# vmuzero_SEPS525_V1_0_ICHG100.net
KiCad netlist of a schematic drawn in EAGLE
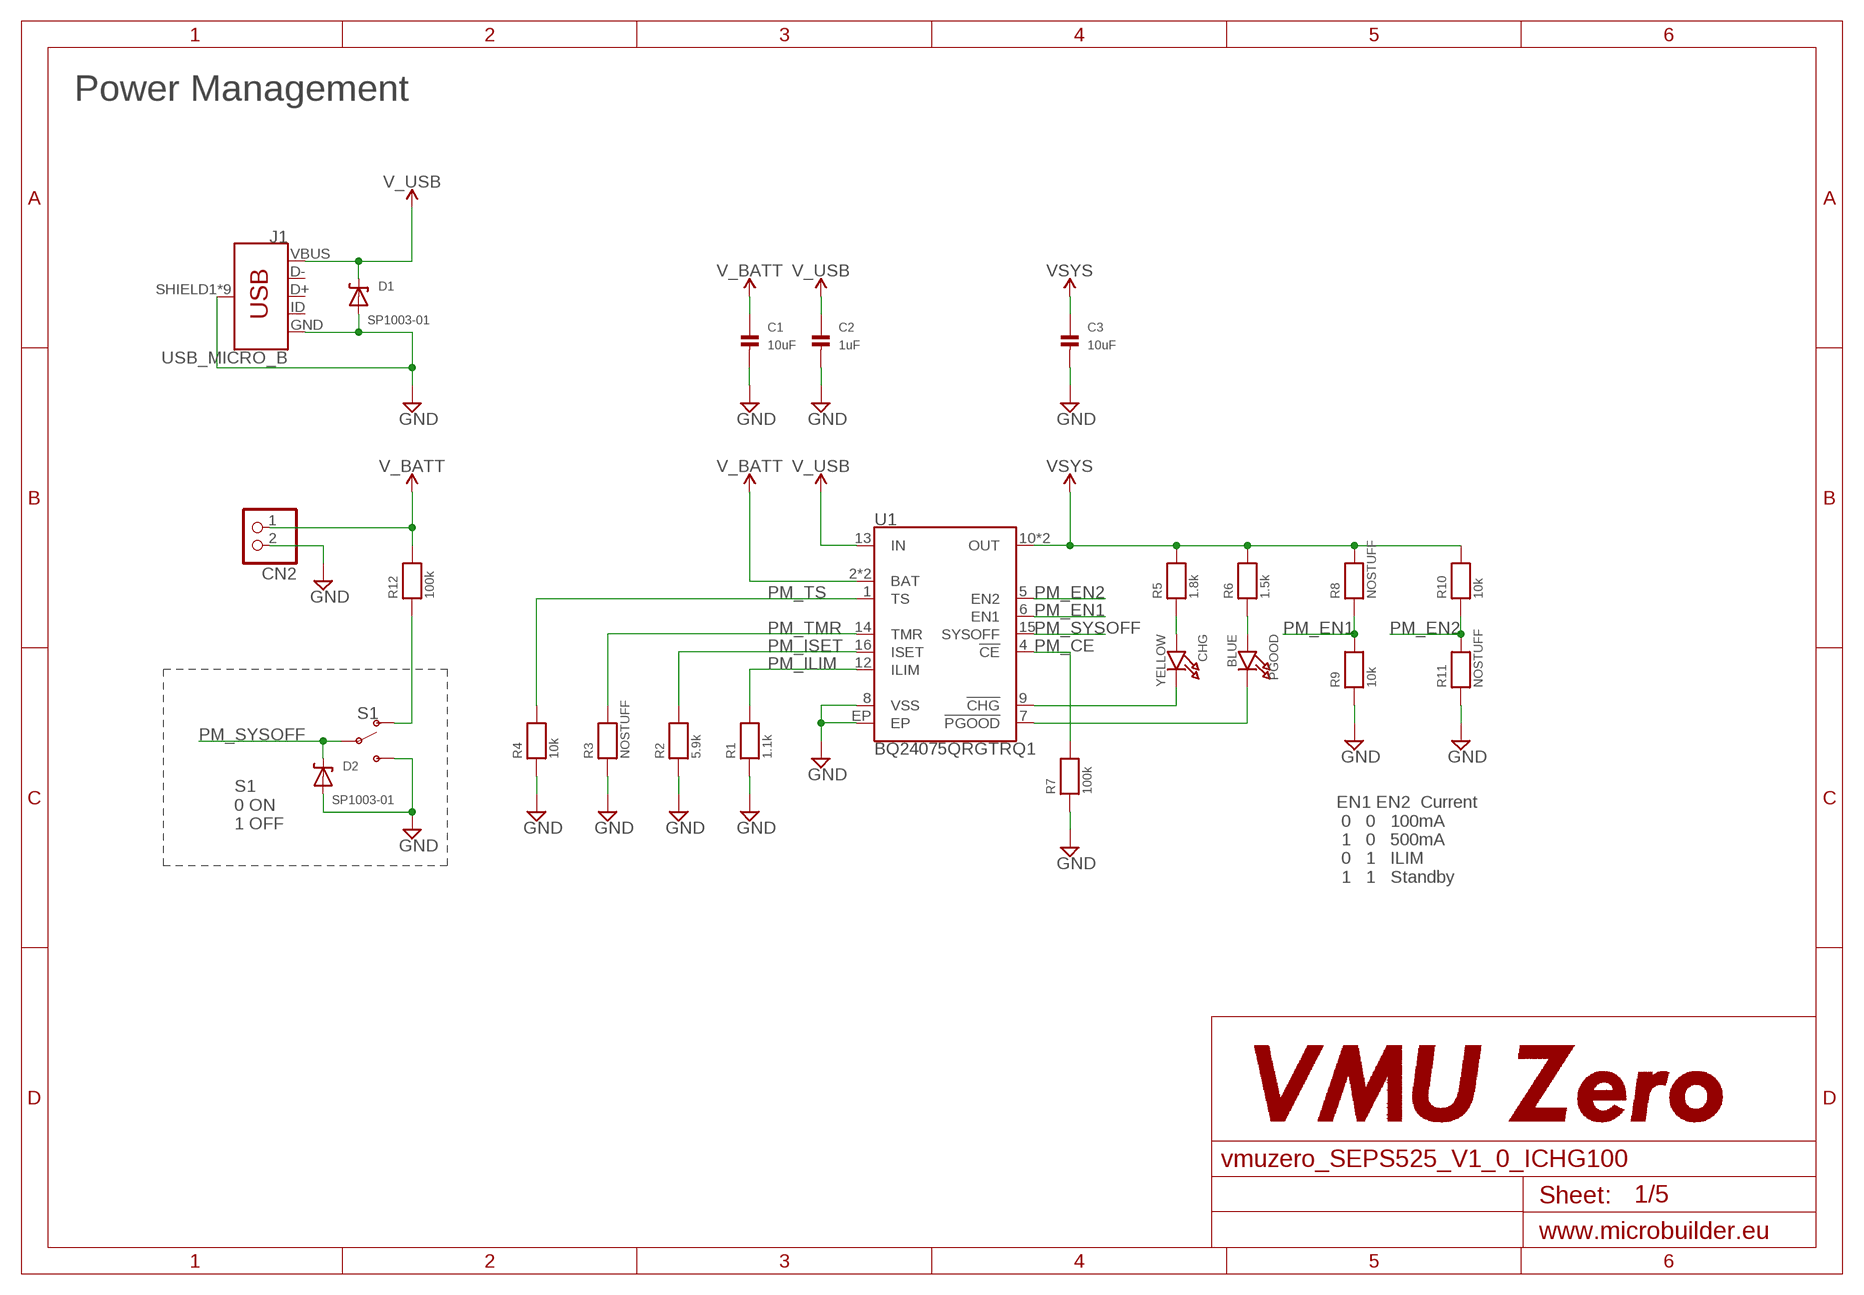
[diagram p0: schematic, sheet 1]
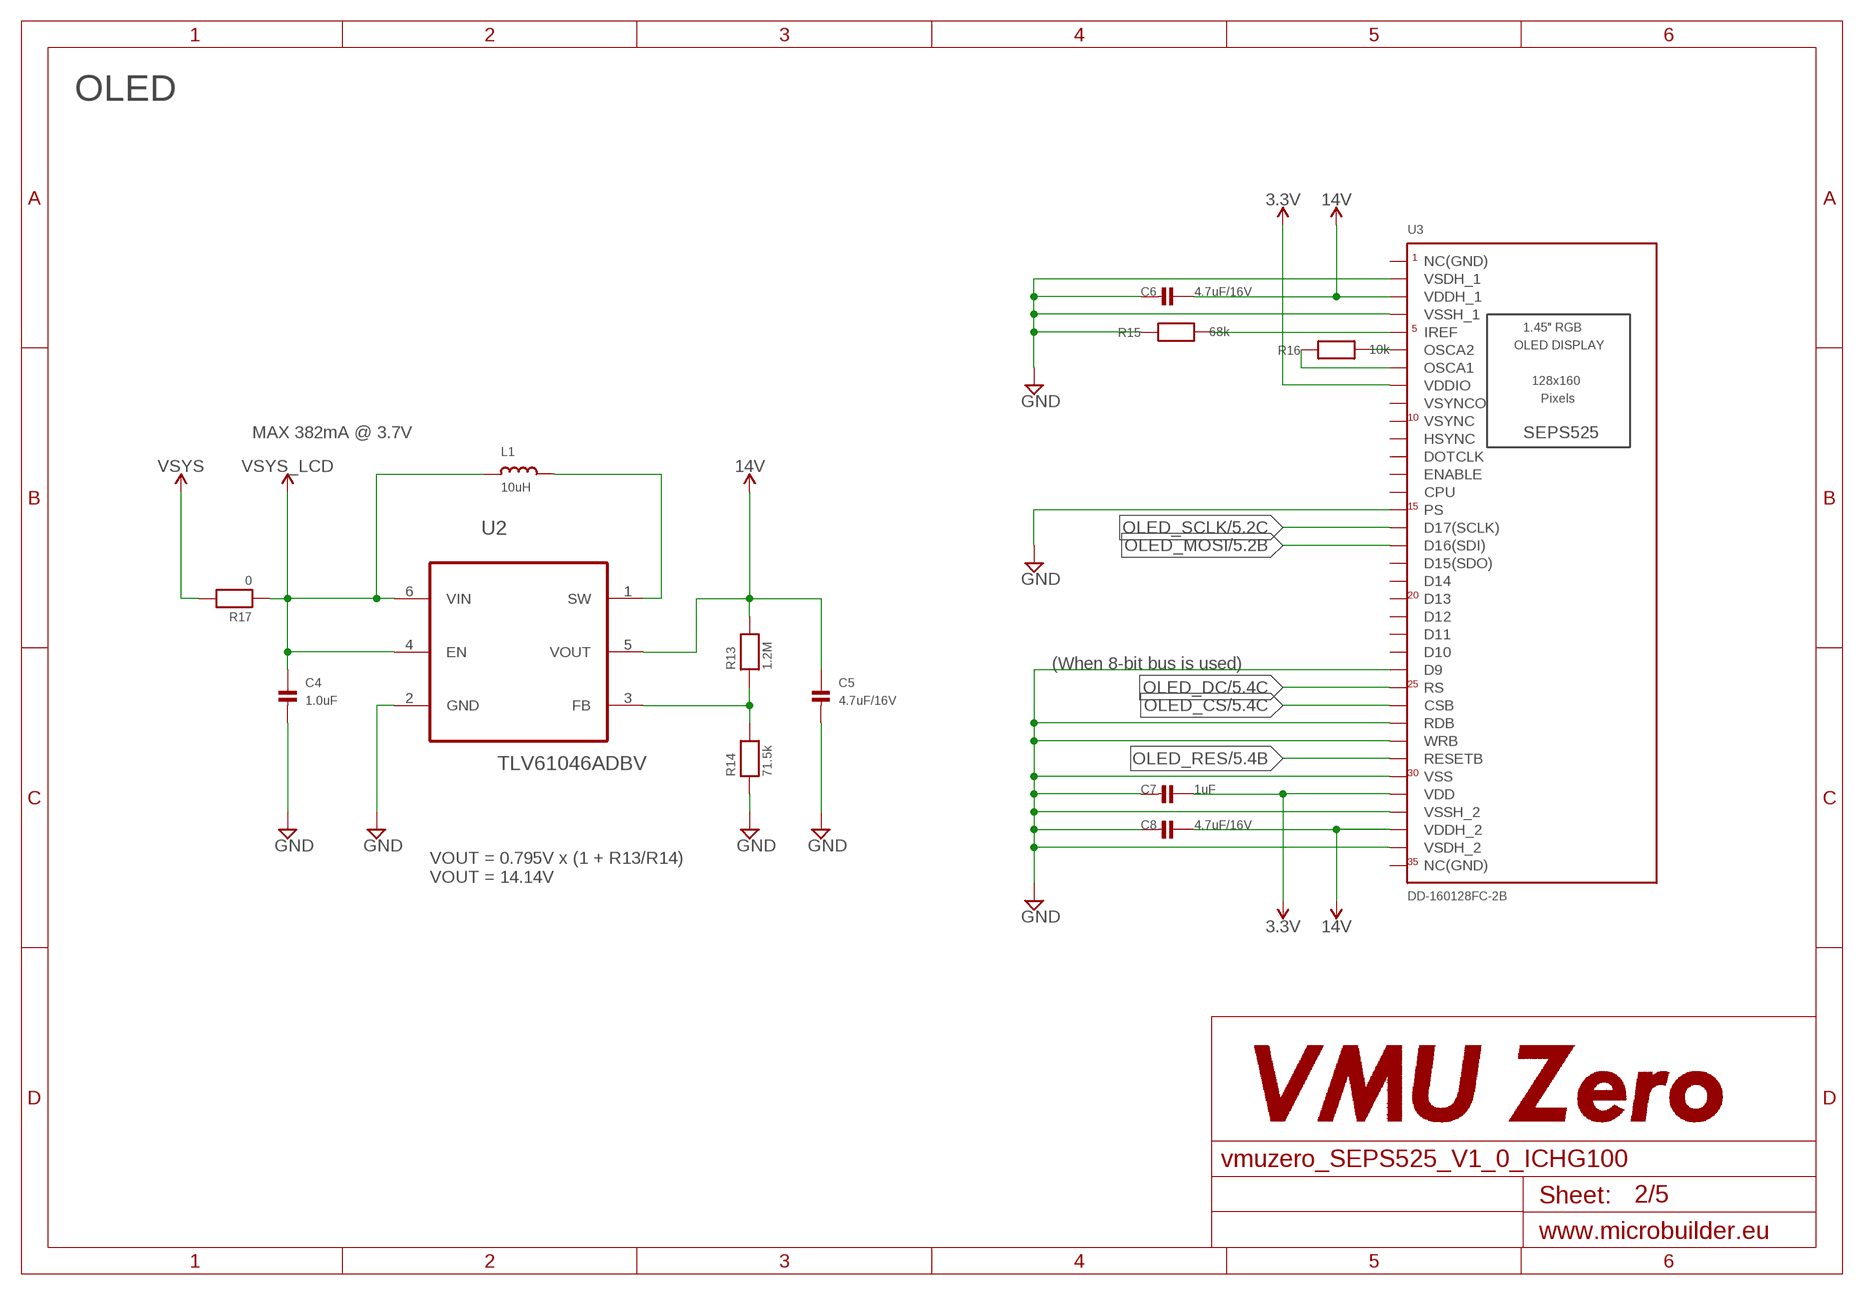
[diagram p1: schematic, sheet 2]
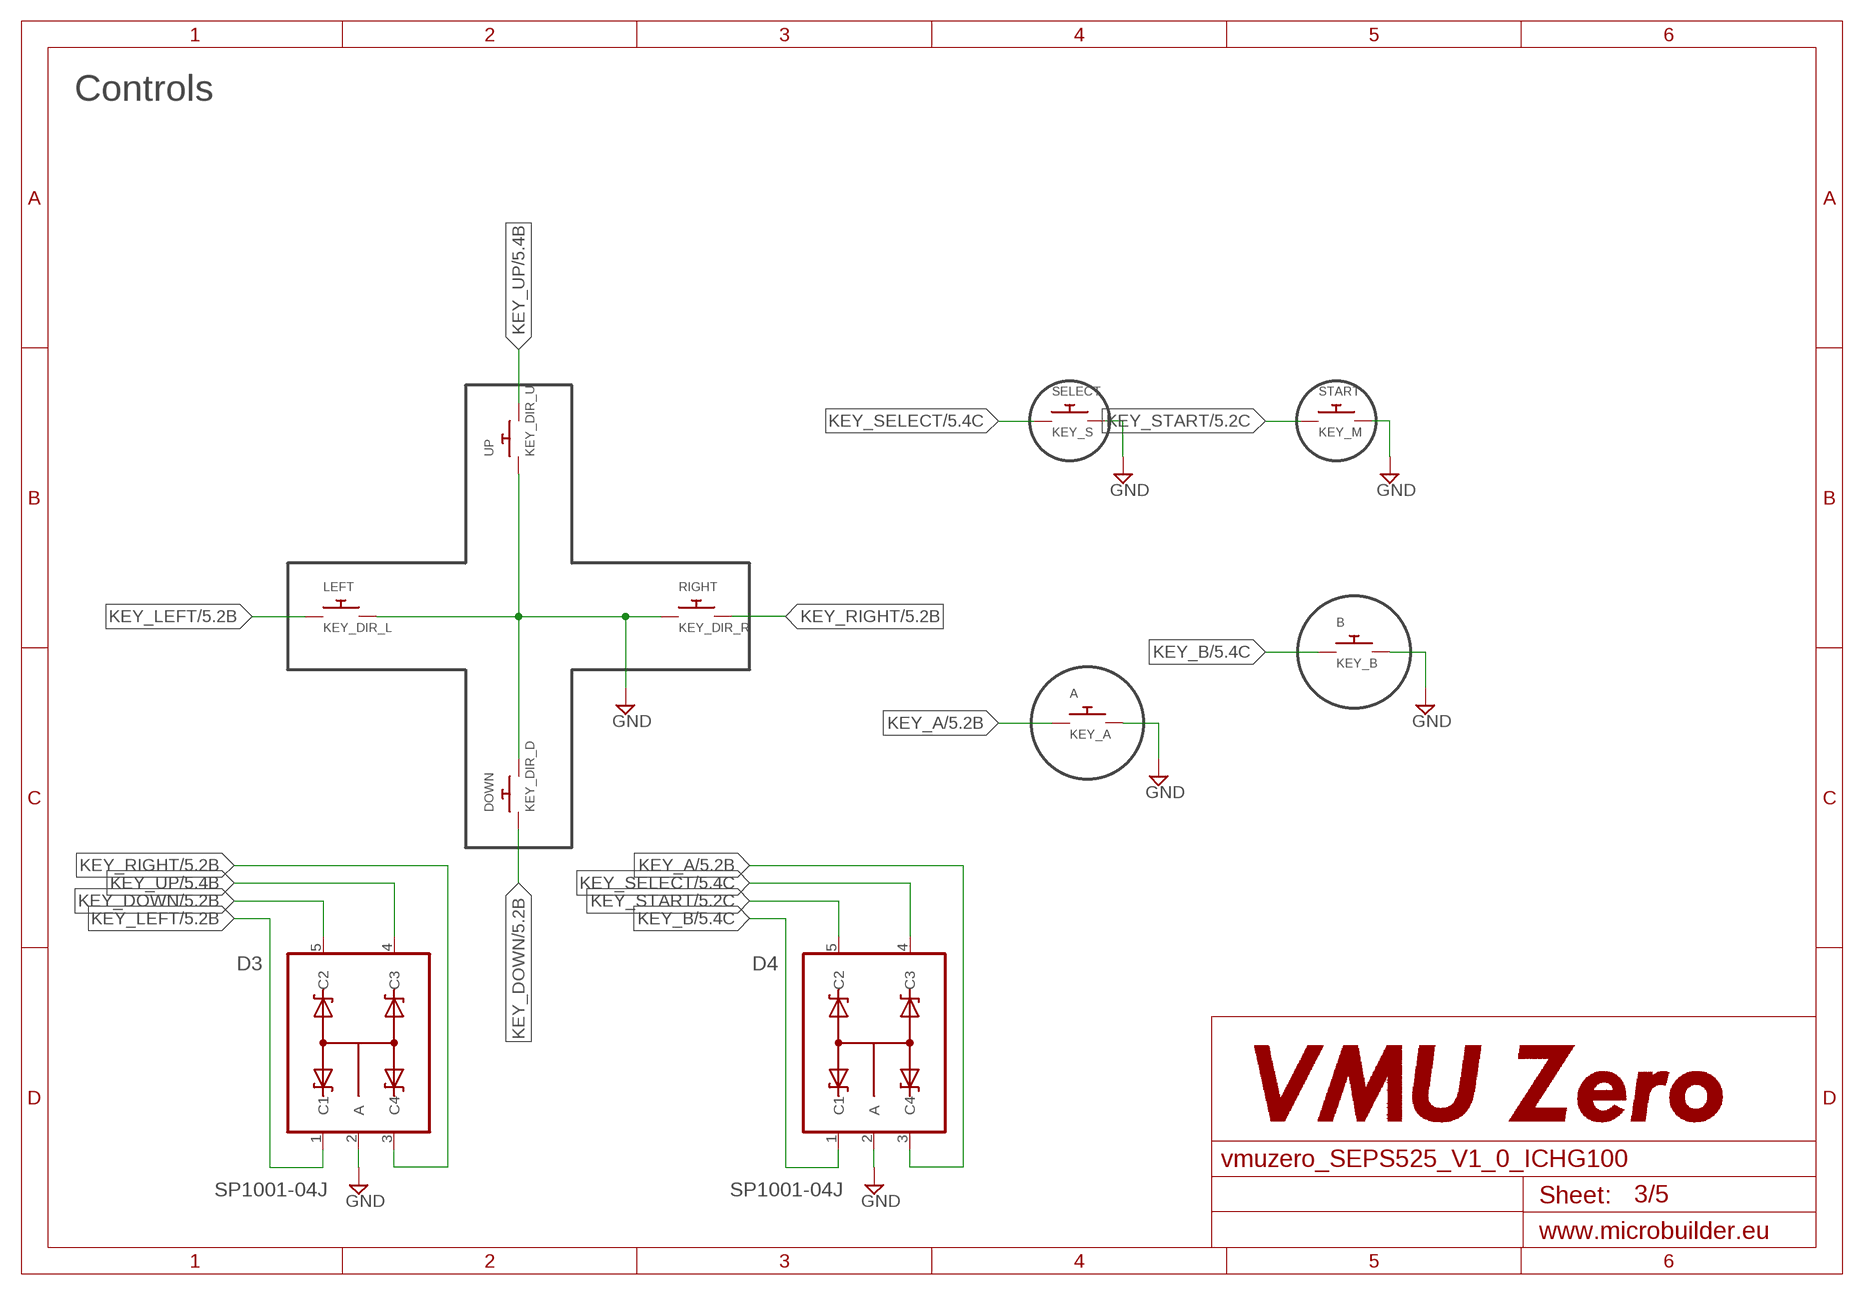
[diagram p2: schematic, sheet 3]
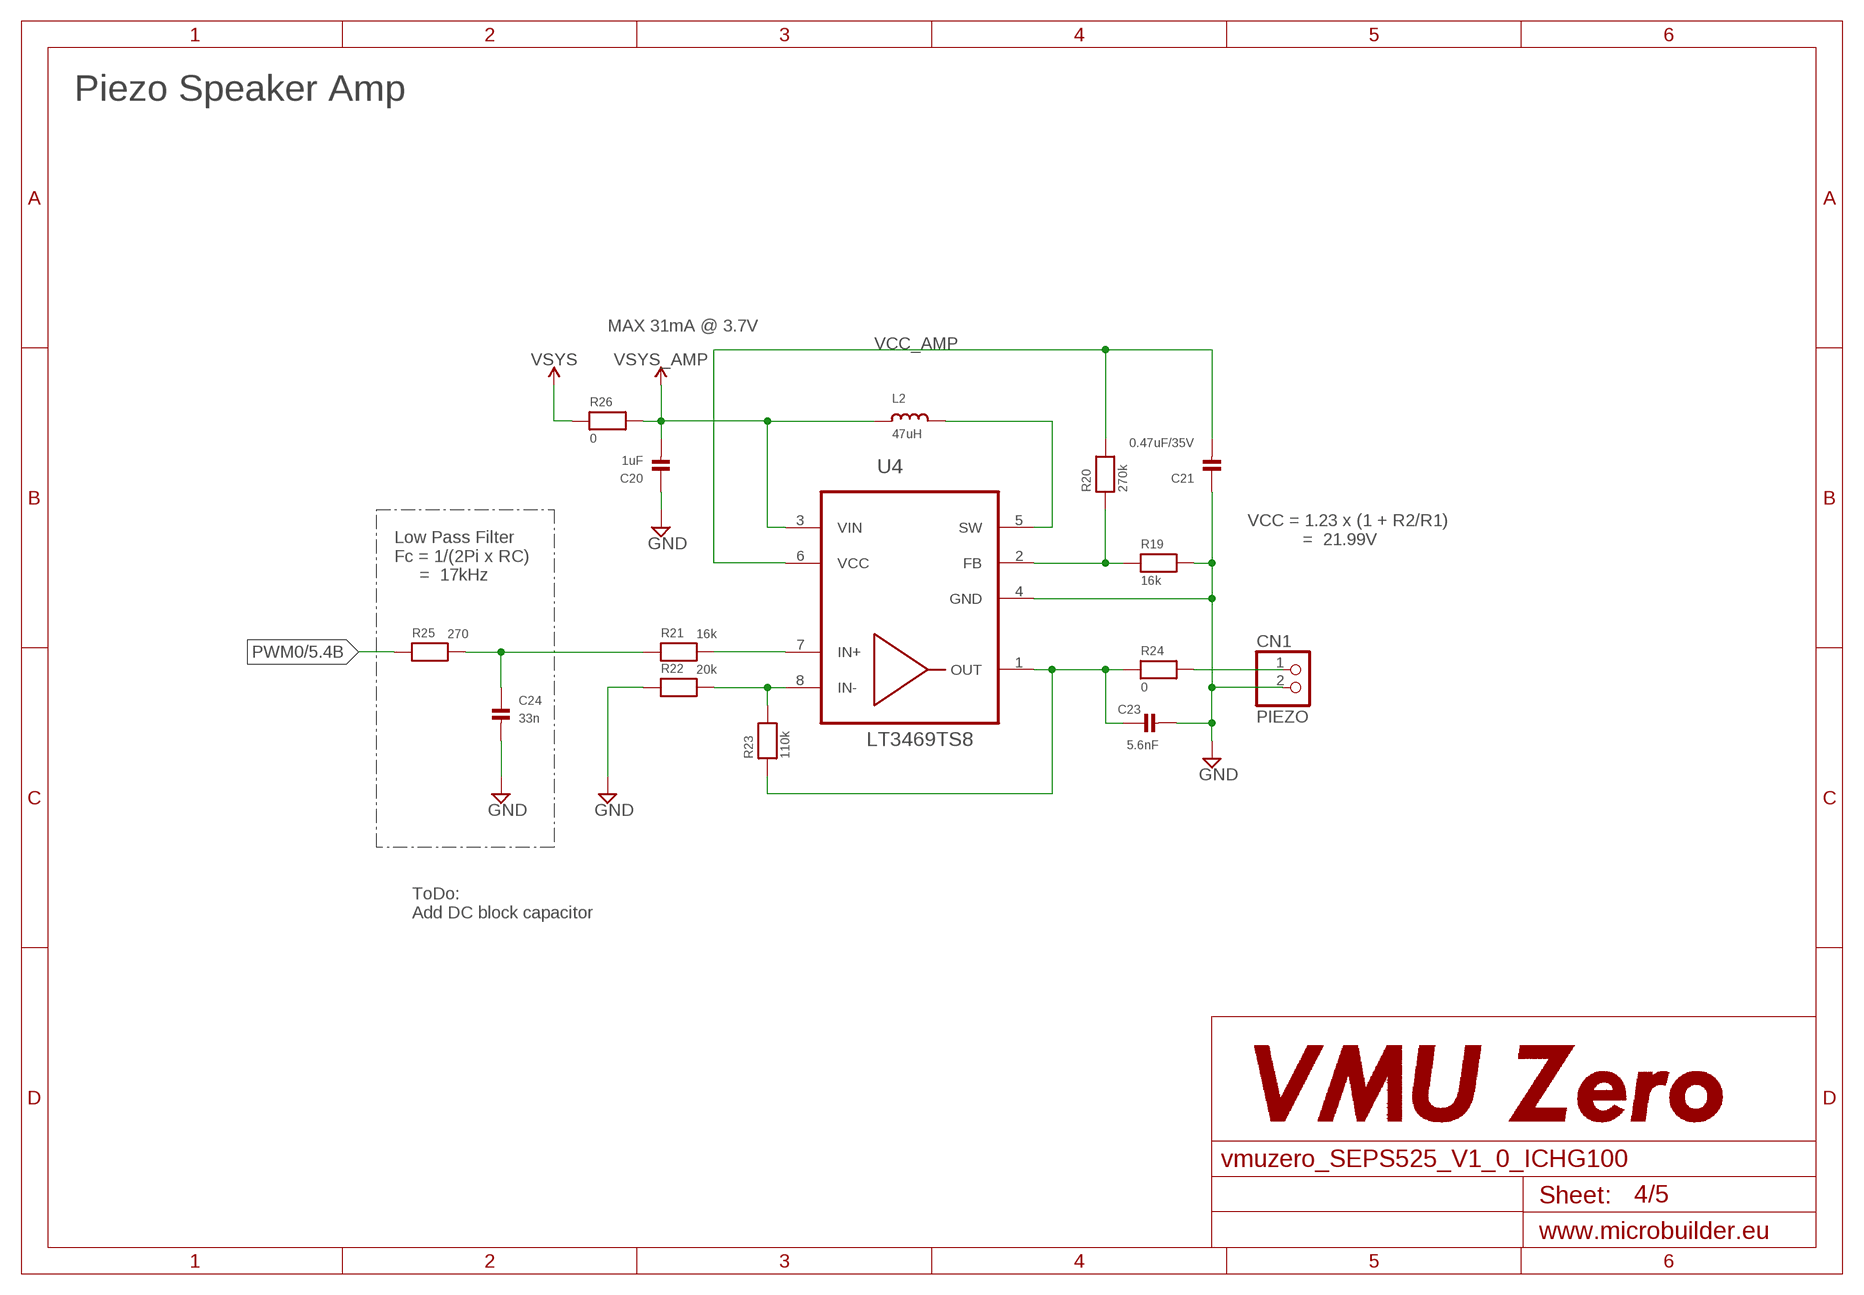
[diagram p3: schematic, sheet 4]
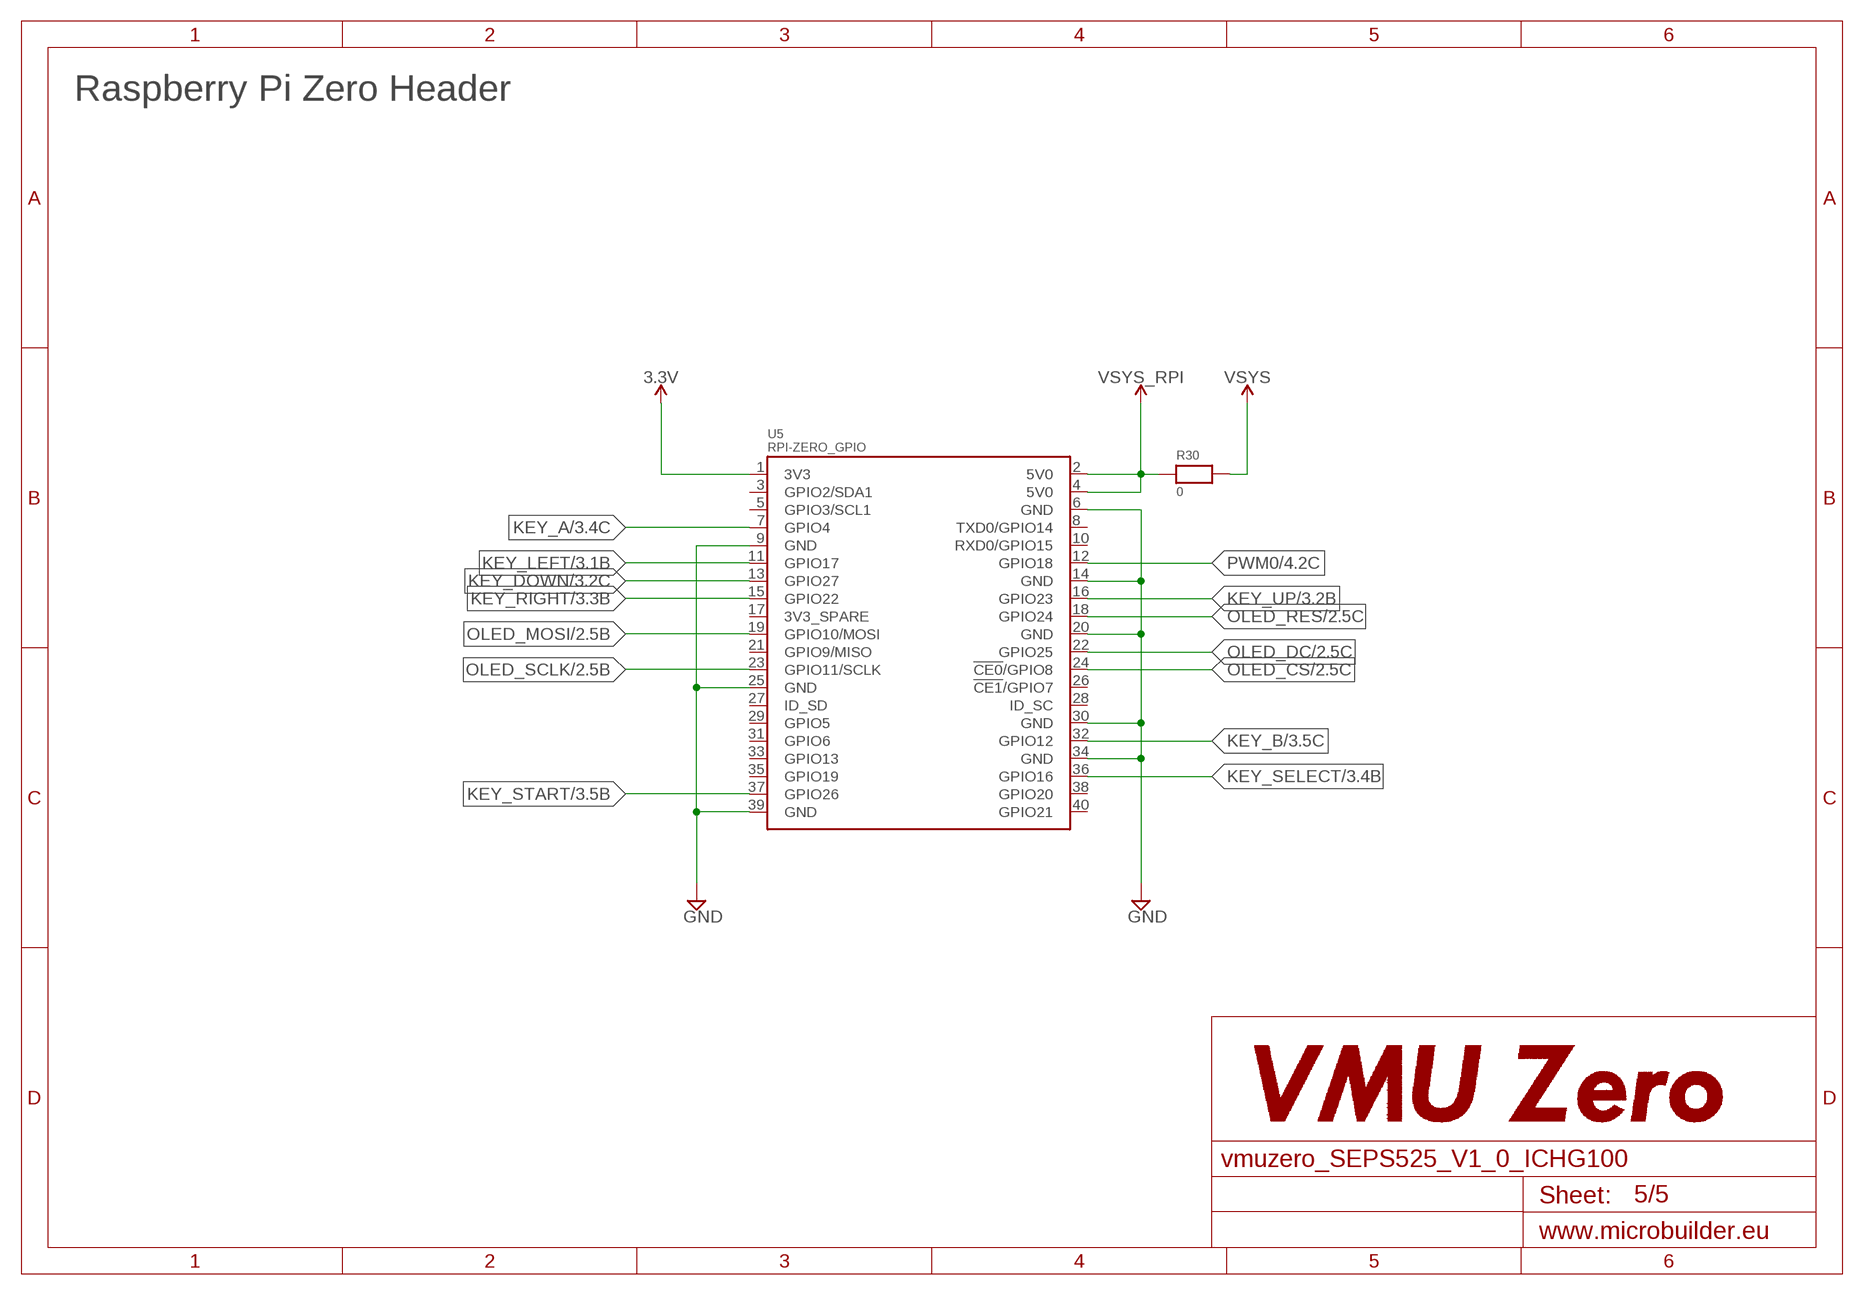
[diagram p4: schematic, sheet 5]

(export (version "E")
  (design (tool "Eeschema 10.0.6"))
  (components
    (comp (ref "C1")
      (value "10uF")
      (footprint "eagle-import:_0805MP")
      (libsource (lib "eagle-import") (part "CAP_CERAMIC_0805MP"))
    )
    (comp (ref "C2")
      (value "1uF")
      (footprint "eagle-import:_0805MP")
      (libsource (lib "eagle-import") (part "CAP_CERAMIC_0805MP"))
    )
    (comp (ref "C3")
      (value "10uF")
      (footprint "eagle-import:_0805MP")
      (libsource (lib "eagle-import") (part "CAP_CERAMIC_0805MP"))
    )
    (comp (ref "CHG")
      (value "YELLOW")
      (footprint "eagle-import:CHIPLED_0805_NOOUTLINE")
      (libsource (lib "eagle-import") (part "LED0805_NOOUTLINE"))
    )
    (comp (ref "CN2")
      (value "JST_2PIN")
      (footprint "eagle-import:S2B-PH-K-S")
      (libsource (lib "eagle-import") (part "JST_2PIN"))
    )
    (comp (ref "D1")
      (value "SP1003-01")
      (footprint "eagle-import:DIODE_SOD723")
      (libsource (lib "eagle-import") (part "SP1003-01D"))
    )
    (comp (ref "D2")
      (value "SP1003-01")
      (footprint "eagle-import:DIODE_SOD723")
      (libsource (lib "eagle-import") (part "SP1003-01D"))
    )
    (comp (ref "J1")
      (value "USB_MICRO_B")
      (footprint "eagle-import:UJ2-MIBH2-4-SMT")
      (fields (field (name "MPN") "UJ2-MIBH-4-SMT"))
      (libsource (lib "eagle-import") (part "USB_MICRO-B_CUI_MIBH2"))
    )
    (comp (ref "PGOOD")
      (value "BLUE")
      (footprint "eagle-import:CHIPLED_0805_NOOUTLINE")
      (libsource (lib "eagle-import") (part "LED0805_NOOUTLINE"))
    )
    (comp (ref "R1")
      (value "1.1k")
      (footprint "eagle-import:_0805MP")
      (libsource (lib "eagle-import") (part "RESISTOR_0805MP"))
    )
    (comp (ref "R2")
      (value "5.9k")
      (footprint "eagle-import:_0805MP")
      (libsource (lib "eagle-import") (part "RESISTOR_0805MP"))
    )
    (comp (ref "R3")
      (value "NOSTUFF")
      (footprint "eagle-import:_0805MP")
      (libsource (lib "eagle-import") (part "RESISTOR_0805MP"))
    )
    (comp (ref "R4")
      (value "10k")
      (footprint "eagle-import:_0805MP")
      (libsource (lib "eagle-import") (part "RESISTOR_0805MP"))
    )
    (comp (ref "R5")
      (value "1.8k")
      (footprint "eagle-import:_0805MP")
      (libsource (lib "eagle-import") (part "RESISTOR_0805MP"))
    )
    (comp (ref "R6")
      (value "1.5k")
      (footprint "eagle-import:_0805MP")
      (libsource (lib "eagle-import") (part "RESISTOR_0805MP"))
    )
    (comp (ref "R7")
      (value "100k")
      (footprint "eagle-import:_0805MP")
      (libsource (lib "eagle-import") (part "RESISTOR_0805MP"))
    )
    (comp (ref "R8")
      (value "NOSTUFF")
      (footprint "eagle-import:_0805MP")
      (libsource (lib "eagle-import") (part "RESISTOR_0805MP"))
    )
    (comp (ref "R9")
      (value "10k")
      (footprint "eagle-import:_0805MP")
      (libsource (lib "eagle-import") (part "RESISTOR_0805MP"))
    )
    (comp (ref "R10")
      (value "10k")
      (footprint "eagle-import:_0805MP")
      (libsource (lib "eagle-import") (part "RESISTOR_0805MP"))
    )
    (comp (ref "R11")
      (value "NOSTUFF")
      (footprint "eagle-import:_0805MP")
      (libsource (lib "eagle-import") (part "RESISTOR_0805MP"))
    )
    (comp (ref "R12")
      (value "100k")
      (footprint "eagle-import:_0805MP")
      (libsource (lib "eagle-import") (part "RESISTOR_0805MP"))
    )
    (comp (ref "S1")
      (value "SWITCH-SPDT")
      (footprint "eagle-import:SPDT_JS102011SAQN")
      (fields (field (name "MPN") "JS102011SAQN"))
      (libsource (lib "eagle-import") (part "SWITCH-SPDT"))
    )
    (comp (ref "U1")
      (value "BQ24075QRGTRQ1")
      (footprint "eagle-import:PVQFN-N16")
      (libsource (lib "eagle-import") (part "BQ24075"))
    )
    (comp (ref "C20")
      (value "1uF")
      (footprint "eagle-import:_0805MP")
      (libsource (lib "eagle-import") (part "CAP_CERAMIC_0805MP"))
    )
    (comp (ref "C21")
      (value "0.47uF/35V")
      (footprint "eagle-import:_0805MP")
      (libsource (lib "eagle-import") (part "CAP_CERAMIC_0805MP"))
    )
    (comp (ref "C23")
      (value "5.6nF")
      (footprint "eagle-import:_0805MP")
      (libsource (lib "eagle-import") (part "CAP_CERAMIC_0805MP"))
    )
    (comp (ref "C24")
      (value "33n")
      (footprint "eagle-import:_0805MP")
      (libsource (lib "eagle-import") (part "CAP_CERAMIC_0805MP"))
    )
    (comp (ref "CN1")
      (value "PIEZO")
      (footprint "eagle-import:1X02_ROUND")
      (libsource (lib "eagle-import") (part "HEADER-1X2ROUND"))
    )
    (comp (ref "L2")
      (value "47uH")
      (footprint "eagle-import:LQH32C")
      (libsource (lib "eagle-import") (part "INDUCTOR_LQH32C"))
    )
    (comp (ref "R19")
      (value "16k")
      (footprint "eagle-import:_0805MP")
      (libsource (lib "eagle-import") (part "RESISTOR_0805MP"))
    )
    (comp (ref "R20")
      (value "270k")
      (footprint "eagle-import:_0805MP")
      (libsource (lib "eagle-import") (part "RESISTOR_0805MP"))
    )
    (comp (ref "R21")
      (value "16k")
      (footprint "eagle-import:_0805MP")
      (libsource (lib "eagle-import") (part "RESISTOR_0805MP"))
    )
    (comp (ref "R22")
      (value "20k")
      (footprint "eagle-import:_0805MP")
      (libsource (lib "eagle-import") (part "RESISTOR_0805MP"))
    )
    (comp (ref "R23")
      (value "110k")
      (footprint "eagle-import:_0805MP")
      (libsource (lib "eagle-import") (part "RESISTOR_0805MP"))
    )
    (comp (ref "R24")
      (value "0")
      (footprint "eagle-import:_0805MP")
      (libsource (lib "eagle-import") (part "RESISTOR_0805MP"))
    )
    (comp (ref "R25")
      (value "270")
      (footprint "eagle-import:_0805MP")
      (libsource (lib "eagle-import") (part "RESISTOR_0805MP"))
    )
    (comp (ref "R26")
      (value "0")
      (footprint "eagle-import:_0805MP")
      (libsource (lib "eagle-import") (part "RESISTOR_0805MP"))
    )
    (comp (ref "U4")
      (value "LT3469TS8")
      (footprint "eagle-import:TSOT-23-8")
      (fields (field (name "MPN") "LT3469ETS8"))
      (libsource (lib "eagle-import") (part "LT3469TS8"))
    )
    (comp (ref "A")
      (value "KEY_A")
      (footprint "eagle-import:KEYPAD_VMU_R26")
      (libsource (lib "eagle-import") (part "SWITCH_PUSH_VMU"))
    )
    (comp (ref "B")
      (value "KEY_B")
      (footprint "eagle-import:KEYPAD_VMU_R26")
      (libsource (lib "eagle-import") (part "SWITCH_PUSH_VMU"))
    )
    (comp (ref "D3")
      (value "SP1001-04J")
      (footprint "eagle-import:SC70-5")
      (fields (field (name "MPN") "SP1001-04"))
      (libsource (lib "eagle-import") (part "SP1001-04J"))
    )
    (comp (ref "D4")
      (value "SP1001-04J")
      (footprint "eagle-import:SC70-5")
      (fields (field (name "MPN") "SP1001-04"))
      (libsource (lib "eagle-import") (part "SP1001-04J"))
    )
    (comp (ref "DOWN")
      (value "KEY_DIR_D")
      (footprint "eagle-import:KEYPAD_VMU_R26")
      (libsource (lib "eagle-import") (part "SWITCH_PUSH_VMU"))
    )
    (comp (ref "LEFT")
      (value "KEY_DIR_L")
      (footprint "eagle-import:KEYPAD_VMU_R26")
      (libsource (lib "eagle-import") (part "SWITCH_PUSH_VMU"))
    )
    (comp (ref "RIGHT")
      (value "KEY_DIR_R")
      (footprint "eagle-import:KEYPAD_VMU_R26")
      (libsource (lib "eagle-import") (part "SWITCH_PUSH_VMU"))
    )
    (comp (ref "SELECT")
      (value "KEY_S")
      (footprint "eagle-import:KEYPAD_VMU_R26")
      (libsource (lib "eagle-import") (part "SWITCH_PUSH_VMU"))
    )
    (comp (ref "START")
      (value "KEY_M")
      (footprint "eagle-import:KEYPAD_VMU_R26")
      (libsource (lib "eagle-import") (part "SWITCH_PUSH_VMU"))
    )
    (comp (ref "UP")
      (value "KEY_DIR_U")
      (footprint "eagle-import:KEYPAD_VMU_R26")
      (libsource (lib "eagle-import") (part "SWITCH_PUSH_VMU"))
    )
    (comp (ref "R30")
      (value "0")
      (footprint "eagle-import:_0805MP")
      (libsource (lib "eagle-import") (part "RESISTOR_0805MP"))
    )
    (comp (ref "U5")
      (value "RPI-ZERO_GPIO")
      (footprint "eagle-import:RASP_PI_ZERO_GPIO_SMD")
      (libsource (lib "eagle-import") (part "RPI-ZERO_GPIO"))
    )
    (comp (ref "C4")
      (value "1.0uF")
      (footprint "eagle-import:_0805MP")
      (libsource (lib "eagle-import") (part "CAP_CERAMIC_0805MP"))
    )
    (comp (ref "C5")
      (value "4.7uF/16V")
      (footprint "eagle-import:_0805MP")
      (libsource (lib "eagle-import") (part "CAP_CERAMIC_0805MP"))
    )
    (comp (ref "C6")
      (value "4.7uF/16V")
      (footprint "eagle-import:_0805MP")
      (libsource (lib "eagle-import") (part "CAP_CERAMIC_0805MP"))
    )
    (comp (ref "C7")
      (value "1uF")
      (footprint "eagle-import:_0805MP")
      (libsource (lib "eagle-import") (part "CAP_CERAMIC_0805MP"))
    )
    (comp (ref "C8")
      (value "4.7uF/16V")
      (footprint "eagle-import:_0805MP")
      (libsource (lib "eagle-import") (part "CAP_CERAMIC_0805MP"))
    )
    (comp (ref "L1")
      (value "10uH")
      (footprint "eagle-import:LQH2")
      (libsource (lib "eagle-import") (part "INDUCTOR_LQH2"))
    )
    (comp (ref "R13")
      (value "1.2M")
      (footprint "eagle-import:_0805MP")
      (libsource (lib "eagle-import") (part "RESISTOR_0805MP"))
    )
    (comp (ref "R14")
      (value "71.5k")
      (footprint "eagle-import:_0805MP")
      (libsource (lib "eagle-import") (part "RESISTOR_0805MP"))
    )
    (comp (ref "R15")
      (value "68k")
      (footprint "eagle-import:_0805MP")
      (libsource (lib "eagle-import") (part "RESISTOR_0805MP"))
    )
    (comp (ref "R16")
      (value "10k")
      (footprint "eagle-import:_0805MP")
      (libsource (lib "eagle-import") (part "RESISTOR_0805MP"))
    )
    (comp (ref "R17")
      (value "0")
      (footprint "eagle-import:_0805MP")
      (libsource (lib "eagle-import") (part "RESISTOR_0805MP"))
    )
    (comp (ref "U2")
      (value "TLV61046ADBV")
      (footprint "eagle-import:R-PDSO-G6")
      (libsource (lib "eagle-import") (part "TLV61046ADBV"))
    )
    (comp (ref "U3")
      (value "DD-160128FC-2B")
      (footprint "eagle-import:XF2M-3515-1A")
      (fields (field (name "MPN") "XF2M-3515-1A"))
      (libsource (lib "eagle-import") (part "DISP_OLED_DD-160128FC-2BNOSWAP"))
    )
  )
  (nets
    (net (code "1") (name "3.3V") (class "Default")
      (node (ref "C7") (pin "1") (pinfunction "P$1_1") (pintype "passive"))
      (node (ref "U3") (pin "31") (pinfunction "VDD_31") (pintype "power_in"))
      (node (ref "U3") (pin "8") (pinfunction "VDDIO_8") (pintype "power_in"))
      (node (ref "U5") (pin "1") (pinfunction "3V3_1") (pintype "power_in"))
    )
    (net (code "2") (name "3V3_SPARE") (class "Default")
      (node (ref "U5") (pin "17") (pinfunction "3V3_SPARE_17") (pintype "power_in"))
    )
    (net (code "3") (name "14V") (class "Default")
      (node (ref "C5") (pin "1") (pinfunction "P$1_1") (pintype "passive"))
      (node (ref "C6") (pin "1") (pinfunction "P$1_1") (pintype "passive"))
      (node (ref "C8") (pin "1") (pinfunction "P$1_1") (pintype "passive"))
      (node (ref "R13") (pin "2") (pinfunction "2_2") (pintype "passive"))
      (node (ref "U2") (pin "5") (pinfunction "VOUT_5") (pintype "passive"))
      (node (ref "U3") (pin "3") (pinfunction "VDDH_1_3") (pintype "power_in"))
      (node (ref "U3") (pin "33") (pinfunction "VDDH_2_33") (pintype "power_in"))
    )
    (net (code "4") (name "GND") (class "Default")
      (node (ref "A") (pin "2") (pinfunction "P$2_2") (pintype "passive"))
      (node (ref "B") (pin "2") (pinfunction "P$2_2") (pintype "passive"))
      (node (ref "C1") (pin "2") (pinfunction "P$2_2") (pintype "passive"))
      (node (ref "C2") (pin "2") (pinfunction "P$2_2") (pintype "passive"))
      (node (ref "C20") (pin "1") (pinfunction "P$1_1") (pintype "passive"))
      (node (ref "C21") (pin "1") (pinfunction "P$1_1") (pintype "passive"))
      (node (ref "C23") (pin "2") (pinfunction "P$2_2") (pintype "passive"))
      (node (ref "C24") (pin "2") (pinfunction "P$2_2") (pintype "passive"))
      (node (ref "C3") (pin "2") (pinfunction "P$2_2") (pintype "passive"))
      (node (ref "C4") (pin "2") (pinfunction "P$2_2") (pintype "passive"))
      (node (ref "C5") (pin "2") (pinfunction "P$2_2") (pintype "passive"))
      (node (ref "C6") (pin "2") (pinfunction "P$2_2") (pintype "passive"))
      (node (ref "C7") (pin "2") (pinfunction "P$2_2") (pintype "passive"))
      (node (ref "C8") (pin "2") (pinfunction "P$2_2") (pintype "passive"))
      (node (ref "CN1") (pin "2") (pinfunction "2_2") (pintype "passive"))
      (node (ref "CN2") (pin "2") (pinfunction "1_2") (pintype "passive"))
      (node (ref "D1") (pin "A") (pinfunction "A_A") (pintype "passive"))
      (node (ref "D2") (pin "A") (pinfunction "A_A") (pintype "passive"))
      (node (ref "D3") (pin "2") (pinfunction "A_2") (pintype "passive"))
      (node (ref "D4") (pin "2") (pinfunction "A_2") (pintype "passive"))
      (node (ref "DOWN") (pin "2") (pinfunction "P$2_2") (pintype "passive"))
      (node (ref "J1") (pin "GND") (pinfunction "GND_GND") (pintype "power_in"))
      (node (ref "J1") (pin "SHIELD1") (pinfunction "SHIELD_SHIELD1") (pintype "bidirectional"))
      (node (ref "J1") (pin "SHIELD10") (pinfunction "SHIELD_SHIELD10") (pintype "bidirectional"))
      (node (ref "J1") (pin "SHIELD2") (pinfunction "SHIELD_SHIELD2") (pintype "bidirectional"))
      (node (ref "J1") (pin "SHIELD3") (pinfunction "SHIELD_SHIELD3") (pintype "bidirectional"))
      (node (ref "J1") (pin "SHIELD5") (pinfunction "SHIELD_SHIELD5") (pintype "bidirectional"))
      (node (ref "J1") (pin "SHIELD6") (pinfunction "SHIELD_SHIELD6") (pintype "bidirectional"))
      (node (ref "J1") (pin "SHIELD7") (pinfunction "SHIELD_SHIELD7") (pintype "bidirectional"))
      (node (ref "J1") (pin "SHIELD8") (pinfunction "SHIELD_SHIELD8") (pintype "bidirectional"))
      (node (ref "J1") (pin "SHIELD9") (pinfunction "SHIELD_SHIELD9") (pintype "bidirectional"))
      (node (ref "LEFT") (pin "2") (pinfunction "P$2_2") (pintype "passive"))
      (node (ref "R1") (pin "1") (pinfunction "1_1") (pintype "passive"))
      (node (ref "R11") (pin "1") (pinfunction "1_1") (pintype "passive"))
      (node (ref "R14") (pin "1") (pinfunction "1_1") (pintype "passive"))
      (node (ref "R15") (pin "2") (pinfunction "2_2") (pintype "passive"))
      (node (ref "R19") (pin "2") (pinfunction "2_2") (pintype "passive"))
      (node (ref "R2") (pin "1") (pinfunction "1_1") (pintype "passive"))
      (node (ref "R22") (pin "1") (pinfunction "1_1") (pintype "passive"))
      (node (ref "R3") (pin "1") (pinfunction "1_1") (pintype "passive"))
      (node (ref "R4") (pin "1") (pinfunction "1_1") (pintype "passive"))
      (node (ref "R7") (pin "1") (pinfunction "1_1") (pintype "passive"))
      (node (ref "R9") (pin "1") (pinfunction "1_1") (pintype "passive"))
      (node (ref "RIGHT") (pin "1") (pinfunction "P$1_1") (pintype "passive"))
      (node (ref "S1") (pin "P$3") (pinfunction "S_P$3") (pintype "passive"))
      (node (ref "SELECT") (pin "2") (pinfunction "P$2_2") (pintype "passive"))
      (node (ref "START") (pin "2") (pinfunction "P$2_2") (pintype "passive"))
      (node (ref "U1") (pin "8") (pinfunction "VSS_8") (pintype "bidirectional"))
      (node (ref "U1") (pin "EP") (pinfunction "EP_EP") (pintype "bidirectional"))
      (node (ref "U2") (pin "2") (pinfunction "GND_2") (pintype "passive"))
      (node (ref "U3") (pin "15") (pinfunction "PS_15") (pintype "bidirectional"))
      (node (ref "U3") (pin "2") (pinfunction "VSDH_1_2") (pintype "passive"))
      (node (ref "U3") (pin "24") (pinfunction "D9_24") (pintype "bidirectional"))
      (node (ref "U3") (pin "27") (pinfunction "RDB_27") (pintype "input"))
      (node (ref "U3") (pin "28") (pinfunction "WRB_28") (pintype "input"))
      (node (ref "U3") (pin "30") (pinfunction "VSS_30") (pintype "passive"))
      (node (ref "U3") (pin "32") (pinfunction "VSSH_2_32") (pintype "passive"))
      (node (ref "U3") (pin "34") (pinfunction "VSDH_2_34") (pintype "passive"))
      (node (ref "U3") (pin "4") (pinfunction "VSSH_1_4") (pintype "passive"))
      (node (ref "U4") (pin "4") (pinfunction "GND_4") (pintype "passive"))
      (node (ref "U5") (pin "14") (pinfunction "GND_14") (pintype "power_in"))
      (node (ref "U5") (pin "20") (pinfunction "GND_20") (pintype "power_in"))
      (node (ref "U5") (pin "25") (pinfunction "GND_25") (pintype "power_in"))
      (node (ref "U5") (pin "30") (pinfunction "GND_30") (pintype "power_in"))
      (node (ref "U5") (pin "34") (pinfunction "GND_34") (pintype "power_in"))
      (node (ref "U5") (pin "39") (pinfunction "GND_39") (pintype "power_in"))
      (node (ref "U5") (pin "6") (pinfunction "GND_6") (pintype "power_in"))
      (node (ref "U5") (pin "9") (pinfunction "GND_9") (pintype "power_in"))
      (node (ref "UP") (pin "1") (pinfunction "P$1_1") (pintype "passive"))
    )
    (net (code "5") (name "KEY_A") (class "Default")
      (node (ref "A") (pin "1") (pinfunction "P$1_1") (pintype "passive"))
      (node (ref "D4") (pin "3") (pinfunction "C4_3") (pintype "passive"))
      (node (ref "U5") (pin "7") (pinfunction "GPIO4_7") (pintype "bidirectional"))
    )
    (net (code "6") (name "KEY_B") (class "Default")
      (node (ref "B") (pin "1") (pinfunction "P$1_1") (pintype "passive"))
      (node (ref "D4") (pin "1") (pinfunction "C1_1") (pintype "passive"))
      (node (ref "U5") (pin "32") (pinfunction "GPIO12_32") (pintype "bidirectional"))
    )
    (net (code "7") (name "KEY_DOWN") (class "Default")
      (node (ref "D3") (pin "5") (pinfunction "C2_5") (pintype "passive"))
      (node (ref "DOWN") (pin "1") (pinfunction "P$1_1") (pintype "passive"))
      (node (ref "U5") (pin "13") (pinfunction "GPIO27_13") (pintype "bidirectional"))
    )
    (net (code "8") (name "KEY_LEFT") (class "Default")
      (node (ref "D3") (pin "1") (pinfunction "C1_1") (pintype "passive"))
      (node (ref "LEFT") (pin "1") (pinfunction "P$1_1") (pintype "passive"))
      (node (ref "U5") (pin "11") (pinfunction "GPIO17_11") (pintype "bidirectional"))
    )
    (net (code "9") (name "KEY_RIGHT") (class "Default")
      (node (ref "D3") (pin "3") (pinfunction "C4_3") (pintype "passive"))
      (node (ref "RIGHT") (pin "2") (pinfunction "P$2_2") (pintype "passive"))
      (node (ref "U5") (pin "15") (pinfunction "GPIO22_15") (pintype "bidirectional"))
    )
    (net (code "10") (name "KEY_SELECT") (class "Default")
      (node (ref "D4") (pin "4") (pinfunction "C3_4") (pintype "passive"))
      (node (ref "SELECT") (pin "1") (pinfunction "P$1_1") (pintype "passive"))
      (node (ref "U5") (pin "36") (pinfunction "GPIO16_36") (pintype "bidirectional"))
    )
    (net (code "11") (name "KEY_START") (class "Default")
      (node (ref "D4") (pin "5") (pinfunction "C2_5") (pintype "passive"))
      (node (ref "START") (pin "1") (pinfunction "P$1_1") (pintype "passive"))
      (node (ref "U5") (pin "37") (pinfunction "GPIO26_37") (pintype "bidirectional"))
    )
    (net (code "12") (name "KEY_UP") (class "Default")
      (node (ref "D3") (pin "4") (pinfunction "C3_4") (pintype "passive"))
      (node (ref "U5") (pin "16") (pinfunction "GPIO23_16") (pintype "bidirectional"))
      (node (ref "UP") (pin "2") (pinfunction "P$2_2") (pintype "passive"))
    )
    (net (code "13") (name "Net-(C23-P$1)") (class "Default")
      (node (ref "C23") (pin "1") (pinfunction "P$1_1") (pintype "passive"))
      (node (ref "R23") (pin "1") (pinfunction "1_1") (pintype "passive"))
      (node (ref "R24") (pin "1") (pinfunction "1_1") (pintype "passive"))
      (node (ref "U4") (pin "1") (pinfunction "OUT_1") (pintype "output"))
    )
    (net (code "14") (name "Net-(C24-P$1)") (class "Default")
      (node (ref "C24") (pin "1") (pinfunction "P$1_1") (pintype "passive"))
      (node (ref "R21") (pin "1") (pinfunction "1_1") (pintype "passive"))
      (node (ref "R25") (pin "2") (pinfunction "2_2") (pintype "passive"))
    )
    (net (code "15") (name "Net-(CHG-PadA)") (class "Default")
      (node (ref "CHG") (pin "A") (pinfunction "A_A") (pintype "passive"))
      (node (ref "R5") (pin "1") (pinfunction "1_1") (pintype "passive"))
    )
    (net (code "16") (name "Net-(CN1-Pad1)") (class "Default")
      (node (ref "CN1") (pin "1") (pinfunction "1_1") (pintype "passive"))
      (node (ref "R24") (pin "2") (pinfunction "2_2") (pintype "passive"))
    )
    (net (code "17") (name "Net-(L1-2)") (class "Default")
      (node (ref "L1") (pin "P$2") (pinfunction "2_P$2") (pintype "passive"))
      (node (ref "U2") (pin "1") (pinfunction "SW_1") (pintype "input"))
    )
    (net (code "18") (name "Net-(L2-2)") (class "Default")
      (node (ref "L2") (pin "P$2") (pinfunction "2_P$2") (pintype "passive"))
      (node (ref "U4") (pin "5") (pinfunction "SW_5") (pintype "output"))
    )
    (net (code "19") (name "Net-(PGOOD-PadA)") (class "Default")
      (node (ref "PGOOD") (pin "A") (pinfunction "A_A") (pintype "passive"))
      (node (ref "R6") (pin "1") (pinfunction "1_1") (pintype "passive"))
    )
    (net (code "20") (name "Net-(S1-O)") (class "Default")
      (node (ref "R12") (pin "1") (pinfunction "1_1") (pintype "passive"))
      (node (ref "S1") (pin "P$1") (pinfunction "O_P$1") (pintype "passive"))
    )
    (net (code "21") (name "Net-(U1-~{CHG})") (class "Default")
      (node (ref "CHG") (pin "C") (pinfunction "C_C") (pintype "passive"))
      (node (ref "U1") (pin "9") (pinfunction "~{CHG}_9") (pintype "bidirectional"))
    )
    (net (code "22") (name "Net-(U1-~{PGOOD})") (class "Default")
      (node (ref "PGOOD") (pin "C") (pinfunction "C_C") (pintype "passive"))
      (node (ref "U1") (pin "7") (pinfunction "~{PGOOD}_7") (pintype "bidirectional"))
    )
    (net (code "23") (name "Net-(U2-FB)") (class "Default")
      (node (ref "R13") (pin "1") (pinfunction "1_1") (pintype "passive"))
      (node (ref "R14") (pin "2") (pinfunction "2_2") (pintype "passive"))
      (node (ref "U2") (pin "3") (pinfunction "FB_3") (pintype "input"))
    )
    (net (code "24") (name "Net-(U3-IREF)") (class "Default")
      (node (ref "R15") (pin "1") (pinfunction "1_1") (pintype "passive"))
      (node (ref "U3") (pin "5") (pinfunction "IREF_5") (pintype "bidirectional"))
    )
    (net (code "25") (name "Net-(U3-OSCA1)") (class "Default")
      (node (ref "R16") (pin "2") (pinfunction "2_2") (pintype "passive"))
      (node (ref "U3") (pin "7") (pinfunction "OSCA1_7") (pintype "bidirectional"))
    )
    (net (code "26") (name "Net-(U3-OSCA2)") (class "Default")
      (node (ref "R16") (pin "1") (pinfunction "1_1") (pintype "passive"))
      (node (ref "U3") (pin "6") (pinfunction "OSCA2_6") (pintype "bidirectional"))
    )
    (net (code "27") (name "Net-(U4-FB)") (class "Default")
      (node (ref "R19") (pin "1") (pinfunction "1_1") (pintype "passive"))
      (node (ref "R20") (pin "1") (pinfunction "1_1") (pintype "passive"))
      (node (ref "U4") (pin "2") (pinfunction "FB_2") (pintype "bidirectional"))
    )
    (net (code "28") (name "Net-(U4-IN+)") (class "Default")
      (node (ref "R21") (pin "2") (pinfunction "2_2") (pintype "passive"))
      (node (ref "U4") (pin "7") (pinfunction "IN+_7") (pintype "input"))
    )
    (net (code "29") (name "Net-(U4-IN-)") (class "Default")
      (node (ref "R22") (pin "2") (pinfunction "2_2") (pintype "passive"))
      (node (ref "R23") (pin "2") (pinfunction "2_2") (pintype "passive"))
      (node (ref "U4") (pin "8") (pinfunction "IN-_8") (pintype "input"))
    )
    (net (code "30") (name "OLED_CS") (class "Default")
      (node (ref "U3") (pin "26") (pinfunction "CSB_26") (pintype "input"))
      (node (ref "U5") (pin "24") (pinfunction "~{CE0}/GPIO8_24") (pintype "bidirectional"))
    )
    (net (code "31") (name "OLED_DC") (class "Default")
      (node (ref "U3") (pin "25") (pinfunction "RS_25") (pintype "input"))
      (node (ref "U5") (pin "22") (pinfunction "GPIO25_22") (pintype "bidirectional"))
    )
    (net (code "32") (name "OLED_MOSI") (class "Default")
      (node (ref "U3") (pin "17") (pinfunction "D16(SDI)_17") (pintype "bidirectional"))
      (node (ref "U5") (pin "19") (pinfunction "GPIO10/MOSI_19") (pintype "bidirectional"))
    )
    (net (code "33") (name "OLED_RES") (class "Default")
      (node (ref "U3") (pin "29") (pinfunction "RESETB_29") (pintype "input"))
      (node (ref "U5") (pin "18") (pinfunction "GPIO24_18") (pintype "bidirectional"))
    )
    (net (code "34") (name "OLED_SCLK") (class "Default")
      (node (ref "U3") (pin "16") (pinfunction "D17(SCLK)_16") (pintype "bidirectional"))
      (node (ref "U5") (pin "23") (pinfunction "GPIO11/SCLK_23") (pintype "bidirectional"))
    )
    (net (code "35") (name "PM_CE") (class "Default")
      (node (ref "R7") (pin "2") (pinfunction "2_2") (pintype "passive"))
      (node (ref "U1") (pin "4") (pinfunction "~{CE}_4") (pintype "bidirectional"))
    )
    (net (code "36") (name "PM_EN1") (class "Default")
      (node (ref "R8") (pin "1") (pinfunction "1_1") (pintype "passive"))
      (node (ref "R9") (pin "2") (pinfunction "2_2") (pintype "passive"))
      (node (ref "U1") (pin "6") (pinfunction "EN1_6") (pintype "bidirectional"))
    )
    (net (code "37") (name "PM_EN2") (class "Default")
      (node (ref "R10") (pin "1") (pinfunction "1_1") (pintype "passive"))
      (node (ref "R11") (pin "2") (pinfunction "2_2") (pintype "passive"))
      (node (ref "U1") (pin "5") (pinfunction "EN2_5") (pintype "bidirectional"))
    )
    (net (code "38") (name "PM_ILIM") (class "Default")
      (node (ref "R1") (pin "2") (pinfunction "2_2") (pintype "passive"))
      (node (ref "U1") (pin "12") (pinfunction "ILIM_12") (pintype "bidirectional"))
    )
    (net (code "39") (name "PM_ISET") (class "Default")
      (node (ref "R2") (pin "2") (pinfunction "2_2") (pintype "passive"))
      (node (ref "U1") (pin "16") (pinfunction "ISET_16") (pintype "bidirectional"))
    )
    (net (code "40") (name "PM_SYSOFF") (class "Default")
      (node (ref "D2") (pin "C") (pinfunction "C_C") (pintype "passive"))
      (node (ref "S1") (pin "P$2") (pinfunction "P_P$2") (pintype "passive"))
      (node (ref "U1") (pin "15") (pinfunction "SYSOFF_15") (pintype "bidirectional"))
    )
    (net (code "41") (name "PM_TMR") (class "Default")
      (node (ref "R3") (pin "2") (pinfunction "2_2") (pintype "passive"))
      (node (ref "U1") (pin "14") (pinfunction "TMR_14") (pintype "bidirectional"))
    )
    (net (code "42") (name "PM_TS") (class "Default")
      (node (ref "R4") (pin "2") (pinfunction "2_2") (pintype "passive"))
      (node (ref "U1") (pin "1") (pinfunction "TS_1") (pintype "bidirectional"))
    )
    (net (code "43") (name "PWM0") (class "Default")
      (node (ref "R25") (pin "1") (pinfunction "1_1") (pintype "passive"))
      (node (ref "U5") (pin "12") (pinfunction "GPIO18_12") (pintype "bidirectional"))
    )
    (net (code "44") (name "VCC_AMP") (class "Default")
      (node (ref "C21") (pin "2") (pinfunction "P$2_2") (pintype "passive"))
      (node (ref "R20") (pin "2") (pinfunction "2_2") (pintype "passive"))
      (node (ref "U4") (pin "6") (pinfunction "VCC_6") (pintype "input"))
    )
    (net (code "45") (name "VSYS") (class "Default")
      (node (ref "C3") (pin "1") (pinfunction "P$1_1") (pintype "passive"))
      (node (ref "R10") (pin "2") (pinfunction "2_2") (pintype "passive"))
      (node (ref "R17") (pin "2") (pinfunction "2_2") (pintype "passive"))
      (node (ref "R26") (pin "1") (pinfunction "1_1") (pintype "passive"))
      (node (ref "R30") (pin "2") (pinfunction "2_2") (pintype "passive"))
      (node (ref "R5") (pin "2") (pinfunction "2_2") (pintype "passive"))
      (node (ref "R6") (pin "2") (pinfunction "2_2") (pintype "passive"))
      (node (ref "R8") (pin "2") (pinfunction "2_2") (pintype "passive"))
      (node (ref "U1") (pin "10") (pinfunction "OUT_10") (pintype "bidirectional"))
      (node (ref "U1") (pin "11") (pinfunction "OUT_11") (pintype "bidirectional"))
    )
    (net (code "46") (name "VSYS_AMP") (class "Default")
      (node (ref "C20") (pin "2") (pinfunction "P$2_2") (pintype "passive"))
      (node (ref "L2") (pin "P$1") (pinfunction "1_P$1") (pintype "passive"))
      (node (ref "R26") (pin "2") (pinfunction "2_2") (pintype "passive"))
      (node (ref "U4") (pin "3") (pinfunction "VIN_3") (pintype "power_in"))
    )
    (net (code "47") (name "VSYS_LCD") (class "Default")
      (node (ref "C4") (pin "1") (pinfunction "P$1_1") (pintype "passive"))
      (node (ref "L1") (pin "P$1") (pinfunction "1_P$1") (pintype "passive"))
      (node (ref "R17") (pin "1") (pinfunction "1_1") (pintype "passive"))
      (node (ref "U2") (pin "4") (pinfunction "EN_4") (pintype "input"))
      (node (ref "U2") (pin "6") (pinfunction "VIN_6") (pintype "power_in"))
    )
    (net (code "48") (name "VSYS_RPI") (class "Default")
      (node (ref "R30") (pin "1") (pinfunction "1_1") (pintype "passive"))
      (node (ref "U5") (pin "2") (pinfunction "5V0_2") (pintype "power_in"))
      (node (ref "U5") (pin "4") (pinfunction "5V0_4") (pintype "power_in"))
    )
    (net (code "49") (name "V_BATT") (class "Default")
      (node (ref "C1") (pin "1") (pinfunction "P$1_1") (pintype "passive"))
      (node (ref "CN2") (pin "1") (pinfunction "2_1") (pintype "passive"))
      (node (ref "R12") (pin "2") (pinfunction "2_2") (pintype "passive"))
      (node (ref "U1") (pin "2") (pinfunction "BAT_2") (pintype "bidirectional"))
      (node (ref "U1") (pin "3") (pinfunction "BAT_3") (pintype "bidirectional"))
    )
    (net (code "50") (name "V_USB") (class "Default")
      (node (ref "C2") (pin "1") (pinfunction "P$1_1") (pintype "passive"))
      (node (ref "D1") (pin "C") (pinfunction "C_C") (pintype "passive"))
      (node (ref "J1") (pin "VBUS") (pinfunction "VBUS_VBUS") (pintype "power_in"))
      (node (ref "U1") (pin "13") (pinfunction "IN_13") (pintype "bidirectional"))
    )
    (net (code "51") (name "unconnected-(J1-PadD+)") (class "Default")
      (node (ref "J1") (pin "D+") (pinfunction "D+_D+") (pintype "bidirectional"))
    )
    (net (code "52") (name "unconnected-(J1-PadD-)") (class "Default")
      (node (ref "J1") (pin "D-") (pinfunction "D-_D-") (pintype "bidirectional"))
    )
    (net (code "53") (name "unconnected-(J1-PadID)") (class "Default")
      (node (ref "J1") (pin "ID") (pinfunction "ID_ID") (pintype "bidirectional"))
    )
    (net (code "54") (name "unconnected-(U3-CPU-Pad14)") (class "Default")
      (node (ref "U3") (pin "14") (pinfunction "CPU_14") (pintype "bidirectional"))
    )
    (net (code "55") (name "unconnected-(U3-D10-Pad23)") (class "Default")
      (node (ref "U3") (pin "23") (pinfunction "D10_23") (pintype "bidirectional"))
    )
    (net (code "56") (name "unconnected-(U3-D11-Pad22)") (class "Default")
      (node (ref "U3") (pin "22") (pinfunction "D11_22") (pintype "bidirectional"))
    )
    (net (code "57") (name "unconnected-(U3-D12-Pad21)") (class "Default")
      (node (ref "U3") (pin "21") (pinfunction "D12_21") (pintype "bidirectional"))
    )
    (net (code "58") (name "unconnected-(U3-D13-Pad20)") (class "Default")
      (node (ref "U3") (pin "20") (pinfunction "D13_20") (pintype "bidirectional"))
    )
    (net (code "59") (name "unconnected-(U3-D14-Pad19)") (class "Default")
      (node (ref "U3") (pin "19") (pinfunction "D14_19") (pintype "bidirectional"))
    )
    (net (code "60") (name "unconnected-(U3-D15(SDO)-Pad18)") (class "Default")
      (node (ref "U3") (pin "18") (pinfunction "D15(SDO)_18") (pintype "bidirectional"))
    )
    (net (code "61") (name "unconnected-(U3-DOTCLK-Pad12)") (class "Default")
      (node (ref "U3") (pin "12") (pinfunction "DOTCLK_12") (pintype "bidirectional"))
    )
    (net (code "62") (name "unconnected-(U3-ENABLE-Pad13)") (class "Default")
      (node (ref "U3") (pin "13") (pinfunction "ENABLE_13") (pintype "bidirectional"))
    )
    (net (code "63") (name "unconnected-(U3-HSYNC-Pad11)") (class "Default")
      (node (ref "U3") (pin "11") (pinfunction "HSYNC_11") (pintype "bidirectional"))
    )
    (net (code "64") (name "unconnected-(U3-NC(GND)-Pad1)") (class "Default")
      (node (ref "U3") (pin "1") (pinfunction "NC(GND)_1") (pintype "no_connect"))
    )
    (net (code "65") (name "unconnected-(U3-NC(GND)-Pad35)") (class "Default")
      (node (ref "U3") (pin "35") (pinfunction "NC(GND)_35") (pintype "no_connect"))
    )
    (net (code "66") (name "unconnected-(U3-VSYNC-Pad10)") (class "Default")
      (node (ref "U3") (pin "10") (pinfunction "VSYNC_10") (pintype "bidirectional"))
    )
    (net (code "67") (name "unconnected-(U3-VSYNCO-Pad9)") (class "Default")
      (node (ref "U3") (pin "9") (pinfunction "VSYNCO_9") (pintype "output"))
    )
    (net (code "68") (name "unconnected-(U5-GPIO2{slash}SDA1-Pad3)") (class "Default")
      (node (ref "U5") (pin "3") (pinfunction "GPIO2/SDA1_3") (pintype "bidirectional"))
    )
    (net (code "69") (name "unconnected-(U5-GPIO3{slash}SCL1-Pad5)") (class "Default")
      (node (ref "U5") (pin "5") (pinfunction "GPIO3/SCL1_5") (pintype "bidirectional"))
    )
    (net (code "70") (name "unconnected-(U5-GPIO5-Pad29)") (class "Default")
      (node (ref "U5") (pin "29") (pinfunction "GPIO5_29") (pintype "bidirectional"))
    )
    (net (code "71") (name "unconnected-(U5-GPIO6-Pad31)") (class "Default")
      (node (ref "U5") (pin "31") (pinfunction "GPIO6_31") (pintype "bidirectional"))
    )
    (net (code "72") (name "unconnected-(U5-GPIO9{slash}MISO-Pad21)") (class "Default")
      (node (ref "U5") (pin "21") (pinfunction "GPIO9/MISO_21") (pintype "bidirectional"))
    )
    (net (code "73") (name "unconnected-(U5-GPIO13-Pad33)") (class "Default")
      (node (ref "U5") (pin "33") (pinfunction "GPIO13_33") (pintype "bidirectional"))
    )
    (net (code "74") (name "unconnected-(U5-GPIO19-Pad35)") (class "Default")
      (node (ref "U5") (pin "35") (pinfunction "GPIO19_35") (pintype "bidirectional"))
    )
    (net (code "75") (name "unconnected-(U5-GPIO20-Pad38)") (class "Default")
      (node (ref "U5") (pin "38") (pinfunction "GPIO20_38") (pintype "bidirectional"))
    )
    (net (code "76") (name "unconnected-(U5-GPIO21-Pad40)") (class "Default")
      (node (ref "U5") (pin "40") (pinfunction "GPIO21_40") (pintype "bidirectional"))
    )
    (net (code "77") (name "unconnected-(U5-ID_SC-Pad28)") (class "Default")
      (node (ref "U5") (pin "28") (pinfunction "ID_SC_28") (pintype "bidirectional"))
    )
    (net (code "78") (name "unconnected-(U5-ID_SD-Pad27)") (class "Default")
      (node (ref "U5") (pin "27") (pinfunction "ID_SD_27") (pintype "bidirectional"))
    )
    (net (code "79") (name "unconnected-(U5-RXD0{slash}GPIO15-Pad10)") (class "Default")
      (node (ref "U5") (pin "10") (pinfunction "RXD0/GPIO15_10") (pintype "bidirectional"))
    )
    (net (code "80") (name "unconnected-(U5-TXD0{slash}GPIO14-Pad8)") (class "Default")
      (node (ref "U5") (pin "8") (pinfunction "TXD0/GPIO14_8") (pintype "bidirectional"))
    )
    (net (code "81") (name "unconnected-(U5-~{CE1}{slash}GPIO7-Pad26)") (class "Default")
      (node (ref "U5") (pin "26") (pinfunction "~{CE1}/GPIO7_26") (pintype "bidirectional"))
    )
  )
)
